# MMC_2_2_MCU.net
KiCad netlist of a schematic drawn in Altium Designer
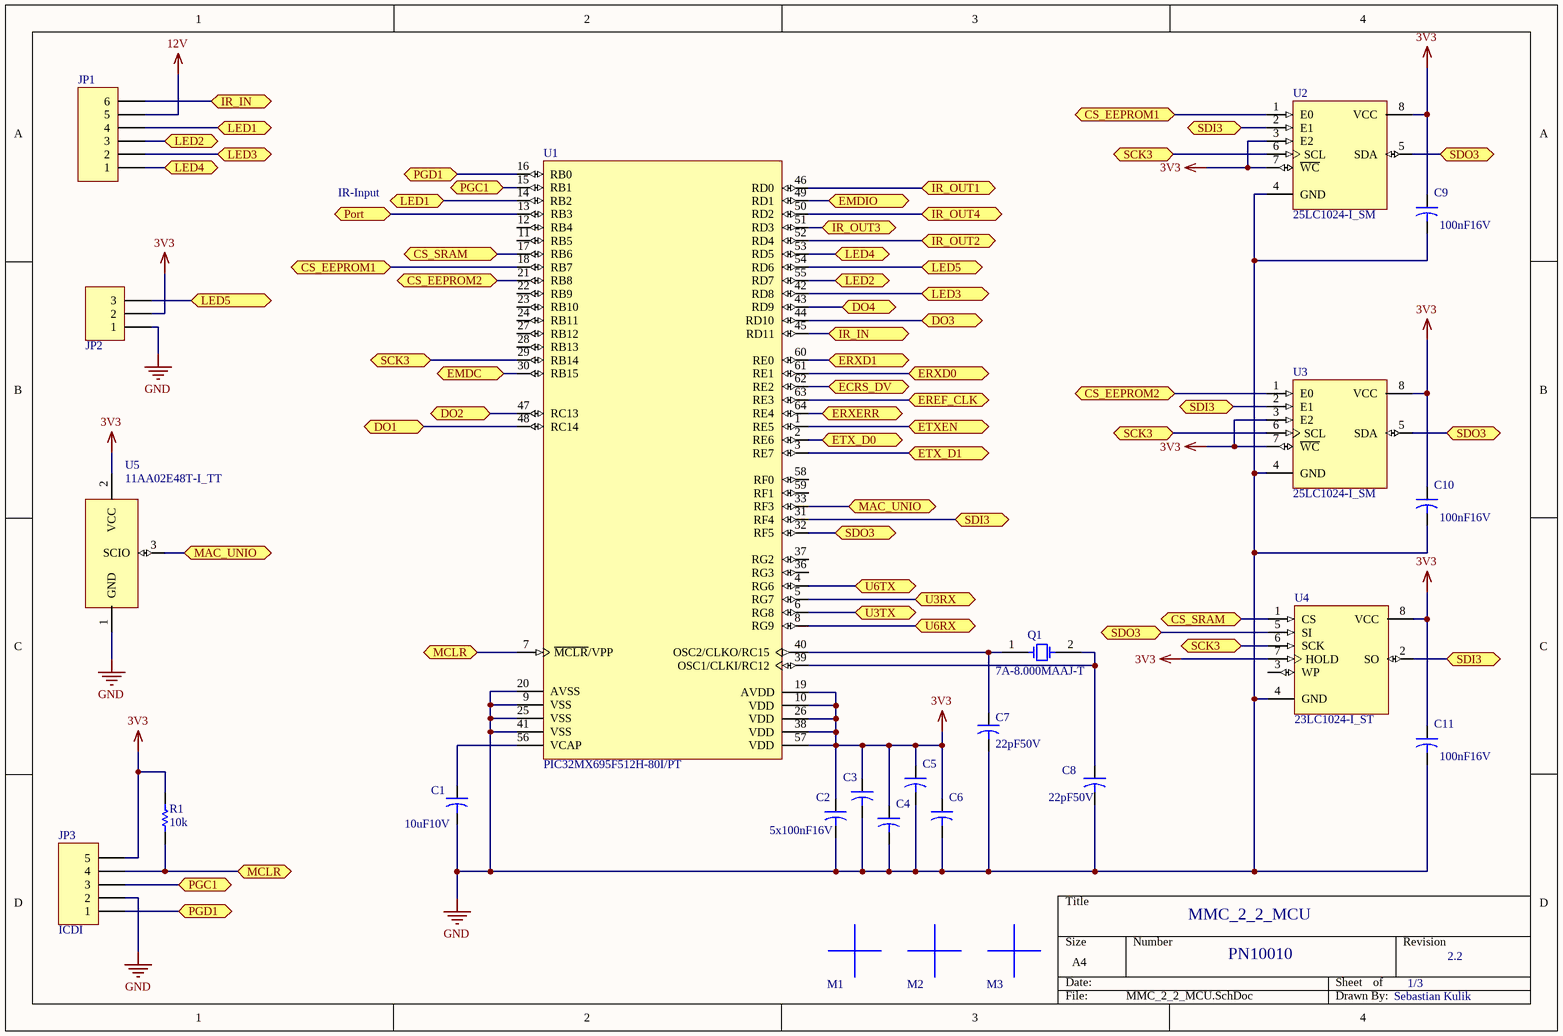
[diagram p0: MMC_2_2_MCU.SchDoc]

(export (version "E")
  (design (tool "Eeschema 10.0.6"))
  (components
    (comp (ref "C1")
      (value "10uF10V")
      (footprint "C0603")
      (description "Capacitor")
      (fields
        (field (name "MANUFACTURER") "AVX")
        (field (name "Comment") "10uF10V_0603")
        (field (name "PUBLISHER") "Sebastian Kulik")
      )
      (libsource (lib "Capacitors") (part "10uF10V_0603"))
    )
    (comp (ref "C2")
      (value "100nF16V_0402")
      (footprint "C0402")
      (description "Capacitor")
      (fields (field (name "MANUFACTURER") "TDK") (field (name "PUBLISHER") "Sebastian Kulik"))
      (libsource (lib "Capacitors") (part "100nF16V_0402"))
    )
    (comp (ref "C3")
      (value "100nF16V_0402")
      (footprint "C0402")
      (description "Capacitor")
      (fields (field (name "MANUFACTURER") "TDK") (field (name "PUBLISHER") "Sebastian Kulik"))
      (libsource (lib "Capacitors") (part "100nF16V_0402"))
    )
    (comp (ref "C4")
      (value "100nF16V_0402")
      (footprint "C0402")
      (description "Capacitor")
      (fields (field (name "MANUFACTURER") "TDK") (field (name "PUBLISHER") "Sebastian Kulik"))
      (libsource (lib "Capacitors") (part "100nF16V_0402"))
    )
    (comp (ref "C5")
      (value "100nF16V_0402")
      (footprint "C0402")
      (description "Capacitor")
      (fields (field (name "MANUFACTURER") "TDK") (field (name "PUBLISHER") "Sebastian Kulik"))
      (libsource (lib "Capacitors") (part "100nF16V_0402"))
    )
    (comp (ref "C6")
      (value "100nF16V_0402")
      (footprint "C0402")
      (description "Capacitor")
      (fields (field (name "MANUFACTURER") "TDK") (field (name "PUBLISHER") "Sebastian Kulik"))
      (libsource (lib "Capacitors") (part "100nF16V_0402"))
    )
    (comp (ref "C7")
      (value "22pF50V")
      (footprint "C0402")
      (description "Murata, GRM series, 50V")
      (fields
        (field (name "MANUFACTURER") "Murata")
        (field (name "Comment") "22pF50V_0402")
        (field (name "PUBLISHER") "Sebastian Kulik")
      )
      (libsource (lib "Capacitors") (part "22pF50V_0402"))
    )
    (comp (ref "C8")
      (value "22pF50V")
      (footprint "C0402")
      (description "Murata, GRM series, 50V")
      (fields
        (field (name "MANUFACTURER") "Murata")
        (field (name "Comment") "22pF50V_0402")
        (field (name "PUBLISHER") "Sebastian Kulik")
      )
      (libsource (lib "Capacitors") (part "22pF50V_0402"))
    )
    (comp (ref "C9")
      (value "100nF16V")
      (footprint "C0402")
      (description "Capacitor")
      (fields
        (field (name "MANUFACTURER") "TDK")
        (field (name "Comment") "100nF16V_0402")
        (field (name "PUBLISHER") "Sebastian Kulik")
      )
      (libsource (lib "Capacitors") (part "100nF16V_0402"))
    )
    (comp (ref "C10")
      (value "100nF16V")
      (footprint "C0402")
      (description "Capacitor")
      (fields
        (field (name "MANUFACTURER") "TDK")
        (field (name "Comment") "100nF16V_0402")
        (field (name "PUBLISHER") "Sebastian Kulik")
      )
      (libsource (lib "Capacitors") (part "100nF16V_0402"))
    )
    (comp (ref "C11")
      (value "100nF16V")
      (footprint "C0402")
      (description "Capacitor")
      (fields
        (field (name "MANUFACTURER") "TDK")
        (field (name "Comment") "100nF16V_0402")
        (field (name "PUBLISHER") "Sebastian Kulik")
      )
      (libsource (lib "Capacitors") (part "100nF16V_0402"))
    )
    (comp (ref "JP1")
      (value "Header 6_2.54")
      (footprint "HDR1X6_2.54")
      (description "Header, 6-Pin")
      (fields (field (name "PUBLISHER") "Altium Limited"))
      (libsource (lib "Connectors") (part "Header 6_2.54"))
    )
    (comp (ref "JP2")
      (value "Header-3")
      (footprint "HDR1X3")
      (description "Header-3-Pin")
      (fields (field (name "PUBLISHER") "Sebastian Kulik"))
      (libsource (lib "Connectors") (part "Header-3"))
    )
    (comp (ref "JP3")
      (value "ICDI")
      (footprint "HDR1X5-1.27")
      (description "Header, 5-Pin")
      (fields (field (name "PUBLISHER") "Sebastian Kulik"))
      (libsource (lib "Connectors") (part "ICDI"))
    )
    (comp (ref "M1") (value "Mark") (footprint "Mark-3mm") (libsource (lib "Symbols") (part "Mark")))
    (comp (ref "M2") (value "Mark") (footprint "Mark-3mm") (libsource (lib "Symbols") (part "Mark")))
    (comp (ref "M3") (value "Mark") (footprint "Mark-3mm") (libsource (lib "Symbols") (part "Mark")))
    (comp (ref "Q1")
      (value "7A-8.000MAAJ-T")
      (footprint "TXC_7A")
      (description "Crystal, 7A-8.000MAAJ-T")
      (fields (field (name "MANUFACTURER") "TXC") (field (name "PUBLISHER") "Sebastian Kulik"))
      (libsource (lib "Passives") (part "Crystal_8MHz"))
    )
    (comp (ref "R1")
      (value "10k")
      (footprint "R0402")
      (description "Vishay CRCW series, 125mW, 1%")
      (fields
        (field (name "MANUFACTURER") "Vishay")
        (field (name "Comment") "10k_0402")
        (field (name "PUBLISHER") "Sebastian Kulik")
      )
      (libsource (lib "Resistors") (part "10k_0402"))
    )
    (comp (ref "U1")
      (value "PIC32MX695F512H-80I/PT")
      (footprint "TQFP-64_N1")
      (fields (field (name "MANUFACTURER") "Microchip") (field (name "PUBLISHER") "Sebastian Kulik"))
      (libsource (lib "ICs") (part "PIC32MX695F512H-80I/PT"))
    )
    (comp (ref "U2")
      (value "25LC1024-I_SM")
      (footprint "SOP8_N")
      (description "1024 Kbit Serial SPI Bus EEPROM")
      (fields (field (name "MANUFACTURER") "Microchip") (field (name "PUBLISHER") "Sebastian Kulik"))
      (libsource (lib "ICs") (part "25LC1024-I_SM"))
    )
    (comp (ref "U3")
      (value "25LC1024-I_SM")
      (footprint "SOP8_N")
      (description "1024 Kbit Serial SPI Bus EEPROM")
      (fields (field (name "MANUFACTURER") "Microchip") (field (name "PUBLISHER") "Sebastian Kulik"))
      (libsource (lib "ICs") (part "25LC1024-I_SM"))
    )
    (comp (ref "U4")
      (value "23LC1024-I_ST")
      (footprint "TSSOP8")
      (description "1 Mbit Serial  EEPROM")
      (fields (field (name "MANUFACTURER") "Microchip") (field (name "PUBLISHER") "Sebastian Kulik"))
      (libsource (lib "ICs") (part "23LC1024-I_ST"))
    )
    (comp (ref "U5")
      (value "11AA02E48T-I_TT")
      (footprint "SOT23_M")
      (description "2 kbit Serial  EEPROM")
      (fields (field (name "MANUFACTURER") "Microchip") (field (name "PUBLISHER") "Sebastian Kulik"))
      (libsource (lib "ICs") (part "11AA02E48T-I_TT"))
    )
  )
  (nets
    (net (code "1") (name "/CS_EEPROM1") (class "Default")
      (node (ref "U1") (pin "18") (pinfunction "RB7_18") (pintype "bidirectional"))
      (node (ref "U2") (pin "1") (pinfunction "E0_1") (pintype "input"))
    )
    (net (code "2") (name "/CS_EEPROM2") (class "Default")
      (node (ref "U1") (pin "21") (pinfunction "RB8_21") (pintype "bidirectional"))
      (node (ref "U3") (pin "1") (pinfunction "E0_1") (pintype "input"))
    )
    (net (code "3") (name "/CS_SRAM") (class "Default")
      (node (ref "U1") (pin "17") (pinfunction "RB6_17") (pintype "bidirectional"))
      (node (ref "U4") (pin "1") (pinfunction "CS_1") (pintype "input"))
    )
    (net (code "4") (name "/DO1") (class "Default")
      (node (ref "U1") (pin "48") (pinfunction "RC14_48") (pintype "bidirectional"))
    )
    (net (code "5") (name "/DO2") (class "Default")
      (node (ref "U1") (pin "47") (pinfunction "RC13_47") (pintype "bidirectional"))
    )
    (net (code "6") (name "/DO3") (class "Default")
      (node (ref "U1") (pin "44") (pinfunction "RD10_44") (pintype "bidirectional"))
    )
    (net (code "7") (name "/DO4") (class "Default")
      (node (ref "U1") (pin "43") (pinfunction "RD9_43") (pintype "bidirectional"))
    )
    (net (code "8") (name "/ECRS_DV") (class "Default")
      (node (ref "U1") (pin "62") (pinfunction "RE2_62") (pintype "bidirectional"))
    )
    (net (code "9") (name "/EMDC") (class "Default")
      (node (ref "U1") (pin "30") (pinfunction "RB15_30") (pintype "bidirectional"))
    )
    (net (code "10") (name "/EMDIO") (class "Default")
      (node (ref "U1") (pin "49") (pinfunction "RD1_49") (pintype "bidirectional"))
    )
    (net (code "11") (name "/EREF_CLK") (class "Default")
      (node (ref "U1") (pin "63") (pinfunction "RE3_63") (pintype "bidirectional"))
    )
    (net (code "12") (name "/ERXD0") (class "Default")
      (node (ref "U1") (pin "61") (pinfunction "RE1_61") (pintype "bidirectional"))
    )
    (net (code "13") (name "/ERXD1") (class "Default")
      (node (ref "U1") (pin "60") (pinfunction "RE0_60") (pintype "bidirectional"))
    )
    (net (code "14") (name "/ERXERR") (class "Default")
      (node (ref "U1") (pin "64") (pinfunction "RE4_64") (pintype "bidirectional"))
    )
    (net (code "15") (name "/ETXEN") (class "Default")
      (node (ref "U1") (pin "1") (pinfunction "RE5_1") (pintype "bidirectional"))
    )
    (net (code "16") (name "/ETX_D0") (class "Default")
      (node (ref "U1") (pin "2") (pinfunction "RE6_2") (pintype "bidirectional"))
    )
    (net (code "17") (name "/ETX_D1") (class "Default")
      (node (ref "U1") (pin "3") (pinfunction "RE7_3") (pintype "bidirectional"))
    )
    (net (code "18") (name "/IR_IN") (class "Default")
      (node (ref "JP1") (pin "6") (pinfunction "6_6") (pintype "passive"))
      (node (ref "U1") (pin "45") (pinfunction "RD11_45") (pintype "bidirectional"))
    )
    (net (code "19") (name "/IR_OUT1") (class "Default")
      (node (ref "U1") (pin "46") (pinfunction "RD0_46") (pintype "bidirectional"))
    )
    (net (code "20") (name "/IR_OUT2") (class "Default")
      (node (ref "U1") (pin "52") (pinfunction "RD4_52") (pintype "bidirectional"))
    )
    (net (code "21") (name "/IR_OUT3") (class "Default")
      (node (ref "U1") (pin "51") (pinfunction "RD3_51") (pintype "bidirectional"))
    )
    (net (code "22") (name "/IR_OUT4") (class "Default")
      (node (ref "U1") (pin "50") (pinfunction "RD2_50") (pintype "bidirectional"))
    )
    (net (code "23") (name "/LED1") (class "Default")
      (node (ref "JP1") (pin "4") (pinfunction "4_4") (pintype "passive"))
      (node (ref "U1") (pin "14") (pinfunction "RB2_14") (pintype "bidirectional"))
    )
    (net (code "24") (name "/LED2") (class "Default")
      (node (ref "JP1") (pin "3") (pinfunction "3_3") (pintype "passive"))
      (node (ref "U1") (pin "55") (pinfunction "RD7_55") (pintype "bidirectional"))
    )
    (net (code "25") (name "/LED3") (class "Default")
      (node (ref "JP1") (pin "2") (pinfunction "2_2") (pintype "passive"))
      (node (ref "U1") (pin "42") (pinfunction "RD8_42") (pintype "bidirectional"))
    )
    (net (code "26") (name "/LED4") (class "Default")
      (node (ref "JP1") (pin "1") (pinfunction "1_1") (pintype "passive"))
      (node (ref "U1") (pin "53") (pinfunction "RD5_53") (pintype "bidirectional"))
    )
    (net (code "27") (name "/LED5") (class "Default")
      (node (ref "JP2") (pin "3") (pinfunction "3_3") (pintype "passive"))
      (node (ref "U1") (pin "54") (pinfunction "RD6_54") (pintype "bidirectional"))
    )
    (net (code "28") (name "/MAC_UNIO") (class "Default")
      (node (ref "U1") (pin "33") (pinfunction "RF3_33") (pintype "bidirectional"))
      (node (ref "U5") (pin "3") (pinfunction "SCIO_3") (pintype "bidirectional"))
    )
    (net (code "29") (name "/MCLR") (class "Default")
      (node (ref "JP3") (pin "4") (pinfunction "4_4") (pintype "passive"))
      (node (ref "R1") (pin "1") (pinfunction "1_1") (pintype "passive"))
      (node (ref "U1") (pin "7") (pinfunction "~{MCLR}/VPP_7") (pintype "input"))
    )
    (net (code "30") (name "/PGC1") (class "Default")
      (node (ref "JP3") (pin "3") (pinfunction "3_3") (pintype "passive"))
      (node (ref "U1") (pin "15") (pinfunction "RB1_15") (pintype "bidirectional"))
    )
    (net (code "31") (name "/PGD1") (class "Default")
      (node (ref "JP3") (pin "1") (pinfunction "1_1") (pintype "passive"))
      (node (ref "U1") (pin "16") (pinfunction "RB0_16") (pintype "bidirectional"))
    )
    (net (code "32") (name "/Port") (class "Default")
      (node (ref "U1") (pin "13") (pinfunction "RB3_13") (pintype "bidirectional"))
    )
    (net (code "33") (name "/SCK3") (class "Default")
      (node (ref "U1") (pin "29") (pinfunction "RB14_29") (pintype "bidirectional"))
      (node (ref "U2") (pin "6") (pinfunction "SCL_6") (pintype "input"))
      (node (ref "U3") (pin "6") (pinfunction "SCL_6") (pintype "input"))
      (node (ref "U4") (pin "6") (pinfunction "SCK_6") (pintype "input"))
    )
    (net (code "34") (name "/SDI3") (class "Default")
      (node (ref "U1") (pin "31") (pinfunction "RF4_31") (pintype "bidirectional"))
      (node (ref "U2") (pin "2") (pinfunction "E1_2") (pintype "input"))
      (node (ref "U3") (pin "2") (pinfunction "E1_2") (pintype "input"))
      (node (ref "U4") (pin "2") (pinfunction "SO_2") (pintype "bidirectional"))
    )
    (net (code "35") (name "/SDO3") (class "Default")
      (node (ref "U1") (pin "32") (pinfunction "RF5_32") (pintype "bidirectional"))
      (node (ref "U2") (pin "5") (pinfunction "SDA_5") (pintype "bidirectional"))
      (node (ref "U3") (pin "5") (pinfunction "SDA_5") (pintype "bidirectional"))
      (node (ref "U4") (pin "5") (pinfunction "SI_5") (pintype "input"))
    )
    (net (code "36") (name "/U3RX") (class "Default")
      (node (ref "U1") (pin "5") (pinfunction "RG7_5") (pintype "bidirectional"))
    )
    (net (code "37") (name "/U3TX") (class "Default")
      (node (ref "U1") (pin "6") (pinfunction "RG8_6") (pintype "bidirectional"))
    )
    (net (code "38") (name "/U6RX") (class "Default")
      (node (ref "U1") (pin "8") (pinfunction "RG9_8") (pintype "bidirectional"))
    )
    (net (code "39") (name "/U6TX") (class "Default")
      (node (ref "U1") (pin "4") (pinfunction "RG6_4") (pintype "bidirectional"))
    )
    (net (code "40") (name "3V3") (class "Default")
      (node (ref "C10") (pin "1") (pinfunction "1_1") (pintype "passive"))
      (node (ref "C11") (pin "1") (pinfunction "1_1") (pintype "passive"))
      (node (ref "C2") (pin "1") (pinfunction "1_1") (pintype "passive"))
      (node (ref "C3") (pin "1") (pinfunction "1_1") (pintype "passive"))
      (node (ref "C4") (pin "1") (pinfunction "1_1") (pintype "passive"))
      (node (ref "C5") (pin "1") (pinfunction "1_1") (pintype "passive"))
      (node (ref "C6") (pin "1") (pinfunction "1_1") (pintype "passive"))
      (node (ref "C9") (pin "1") (pinfunction "1_1") (pintype "passive"))
      (node (ref "JP2") (pin "2") (pinfunction "2_2") (pintype "passive"))
      (node (ref "JP3") (pin "5") (pinfunction "5_5") (pintype "passive"))
      (node (ref "R1") (pin "2") (pinfunction "2_2") (pintype "passive"))
      (node (ref "U1") (pin "10") (pinfunction "VDD_10") (pintype "power_in"))
      (node (ref "U1") (pin "19") (pinfunction "AVDD_19") (pintype "power_in"))
      (node (ref "U1") (pin "26") (pinfunction "VDD_26") (pintype "power_in"))
      (node (ref "U1") (pin "38") (pinfunction "VDD_38") (pintype "power_in"))
      (node (ref "U1") (pin "57") (pinfunction "VDD_57") (pintype "power_in"))
      (node (ref "U2") (pin "3") (pinfunction "E2_3") (pintype "input"))
      (node (ref "U2") (pin "7") (pinfunction "~{WC}_7") (pintype "bidirectional"))
      (node (ref "U2") (pin "8") (pinfunction "VCC_8") (pintype "power_in"))
      (node (ref "U3") (pin "3") (pinfunction "E2_3") (pintype "input"))
      (node (ref "U3") (pin "7") (pinfunction "~{WC}_7") (pintype "bidirectional"))
      (node (ref "U3") (pin "8") (pinfunction "VCC_8") (pintype "power_in"))
      (node (ref "U4") (pin "7") (pinfunction "HOLD_7") (pintype "input"))
      (node (ref "U4") (pin "8") (pinfunction "VCC_8") (pintype "power_in"))
      (node (ref "U5") (pin "2") (pinfunction "VCC_2") (pintype "power_in"))
    )
    (net (code "41") (name "12V") (class "Default")
      (node (ref "JP1") (pin "5") (pinfunction "5_5") (pintype "passive"))
    )
    (net (code "42") (name "GND") (class "Default")
      (node (ref "C1") (pin "2") (pinfunction "2_2") (pintype "passive"))
      (node (ref "C10") (pin "2") (pinfunction "2_2") (pintype "passive"))
      (node (ref "C11") (pin "2") (pinfunction "2_2") (pintype "passive"))
      (node (ref "C2") (pin "2") (pinfunction "2_2") (pintype "passive"))
      (node (ref "C3") (pin "2") (pinfunction "2_2") (pintype "passive"))
      (node (ref "C4") (pin "2") (pinfunction "2_2") (pintype "passive"))
      (node (ref "C5") (pin "2") (pinfunction "2_2") (pintype "passive"))
      (node (ref "C6") (pin "2") (pinfunction "2_2") (pintype "passive"))
      (node (ref "C7") (pin "2") (pinfunction "2_2") (pintype "passive"))
      (node (ref "C8") (pin "2") (pinfunction "2_2") (pintype "passive"))
      (node (ref "C9") (pin "2") (pinfunction "2_2") (pintype "passive"))
      (node (ref "JP2") (pin "1") (pinfunction "1_1") (pintype "passive"))
      (node (ref "JP3") (pin "2") (pinfunction "2_2") (pintype "passive"))
      (node (ref "U1") (pin "20") (pinfunction "AVSS_20") (pintype "power_in"))
      (node (ref "U1") (pin "25") (pinfunction "VSS_25") (pintype "power_in"))
      (node (ref "U1") (pin "41") (pinfunction "VSS_41") (pintype "power_in"))
      (node (ref "U1") (pin "9") (pinfunction "VSS_9") (pintype "power_in"))
      (node (ref "U2") (pin "4") (pinfunction "GND_4") (pintype "power_in"))
      (node (ref "U3") (pin "4") (pinfunction "GND_4") (pintype "power_in"))
      (node (ref "U4") (pin "4") (pinfunction "GND_4") (pintype "power_in"))
      (node (ref "U5") (pin "1") (pinfunction "GND_1") (pintype "power_in"))
    )
    (net (code "43") (name "Net-(Q1-E{slash}D)") (class "Default")
      (node (ref "C7") (pin "1") (pinfunction "1_1") (pintype "passive"))
      (node (ref "Q1") (pin "1") (pinfunction "E/D_1") (pintype "passive"))
      (node (ref "U1") (pin "40") (pinfunction "OSC2/CLKO/RC15_40") (pintype "output"))
    )
    (net (code "44") (name "Net-(Q1-GND)") (class "Default")
      (node (ref "C8") (pin "1") (pinfunction "1_1") (pintype "passive"))
      (node (ref "Q1") (pin "2") (pinfunction "GND_2") (pintype "passive"))
      (node (ref "U1") (pin "39") (pinfunction "OSC1/CLKI/RC12_39") (pintype "bidirectional"))
    )
    (net (code "45") (name "Net-(U1-VCAP)") (class "Default")
      (node (ref "C1") (pin "1") (pinfunction "1_1") (pintype "passive"))
      (node (ref "U1") (pin "56") (pinfunction "VCAP_56") (pintype "power_in"))
    )
    (net (code "46") (name "unconnected-(U1-RB4-Pad12)") (class "Default")
      (node (ref "U1") (pin "12") (pinfunction "RB4_12") (pintype "bidirectional"))
    )
    (net (code "47") (name "unconnected-(U1-RB5-Pad11)") (class "Default")
      (node (ref "U1") (pin "11") (pinfunction "RB5_11") (pintype "bidirectional"))
    )
    (net (code "48") (name "unconnected-(U1-RB9-Pad22)") (class "Default")
      (node (ref "U1") (pin "22") (pinfunction "RB9_22") (pintype "bidirectional"))
    )
    (net (code "49") (name "unconnected-(U1-RB10-Pad23)") (class "Default")
      (node (ref "U1") (pin "23") (pinfunction "RB10_23") (pintype "bidirectional"))
    )
    (net (code "50") (name "unconnected-(U1-RB11-Pad24)") (class "Default")
      (node (ref "U1") (pin "24") (pinfunction "RB11_24") (pintype "bidirectional"))
    )
    (net (code "51") (name "unconnected-(U1-RB12-Pad27)") (class "Default")
      (node (ref "U1") (pin "27") (pinfunction "RB12_27") (pintype "bidirectional"))
    )
    (net (code "52") (name "unconnected-(U1-RB13-Pad28)") (class "Default")
      (node (ref "U1") (pin "28") (pinfunction "RB13_28") (pintype "bidirectional"))
    )
    (net (code "53") (name "unconnected-(U1-RF0-Pad58)") (class "Default")
      (node (ref "U1") (pin "58") (pinfunction "RF0_58") (pintype "bidirectional"))
    )
    (net (code "54") (name "unconnected-(U1-RF1-Pad59)") (class "Default")
      (node (ref "U1") (pin "59") (pinfunction "RF1_59") (pintype "bidirectional"))
    )
    (net (code "55") (name "unconnected-(U1-RG2-Pad37)") (class "Default")
      (node (ref "U1") (pin "37") (pinfunction "RG2_37") (pintype "bidirectional"))
    )
    (net (code "56") (name "unconnected-(U1-RG3-Pad36)") (class "Default")
      (node (ref "U1") (pin "36") (pinfunction "RG3_36") (pintype "bidirectional"))
    )
    (net (code "57") (name "unconnected-(U4-WP-Pad3)") (class "Default")
      (node (ref "U4") (pin "3") (pinfunction "WP_3") (pintype "bidirectional"))
    )
  )
)
